# Board.net
KiCad netlist of a schematic drawn in EAGLE
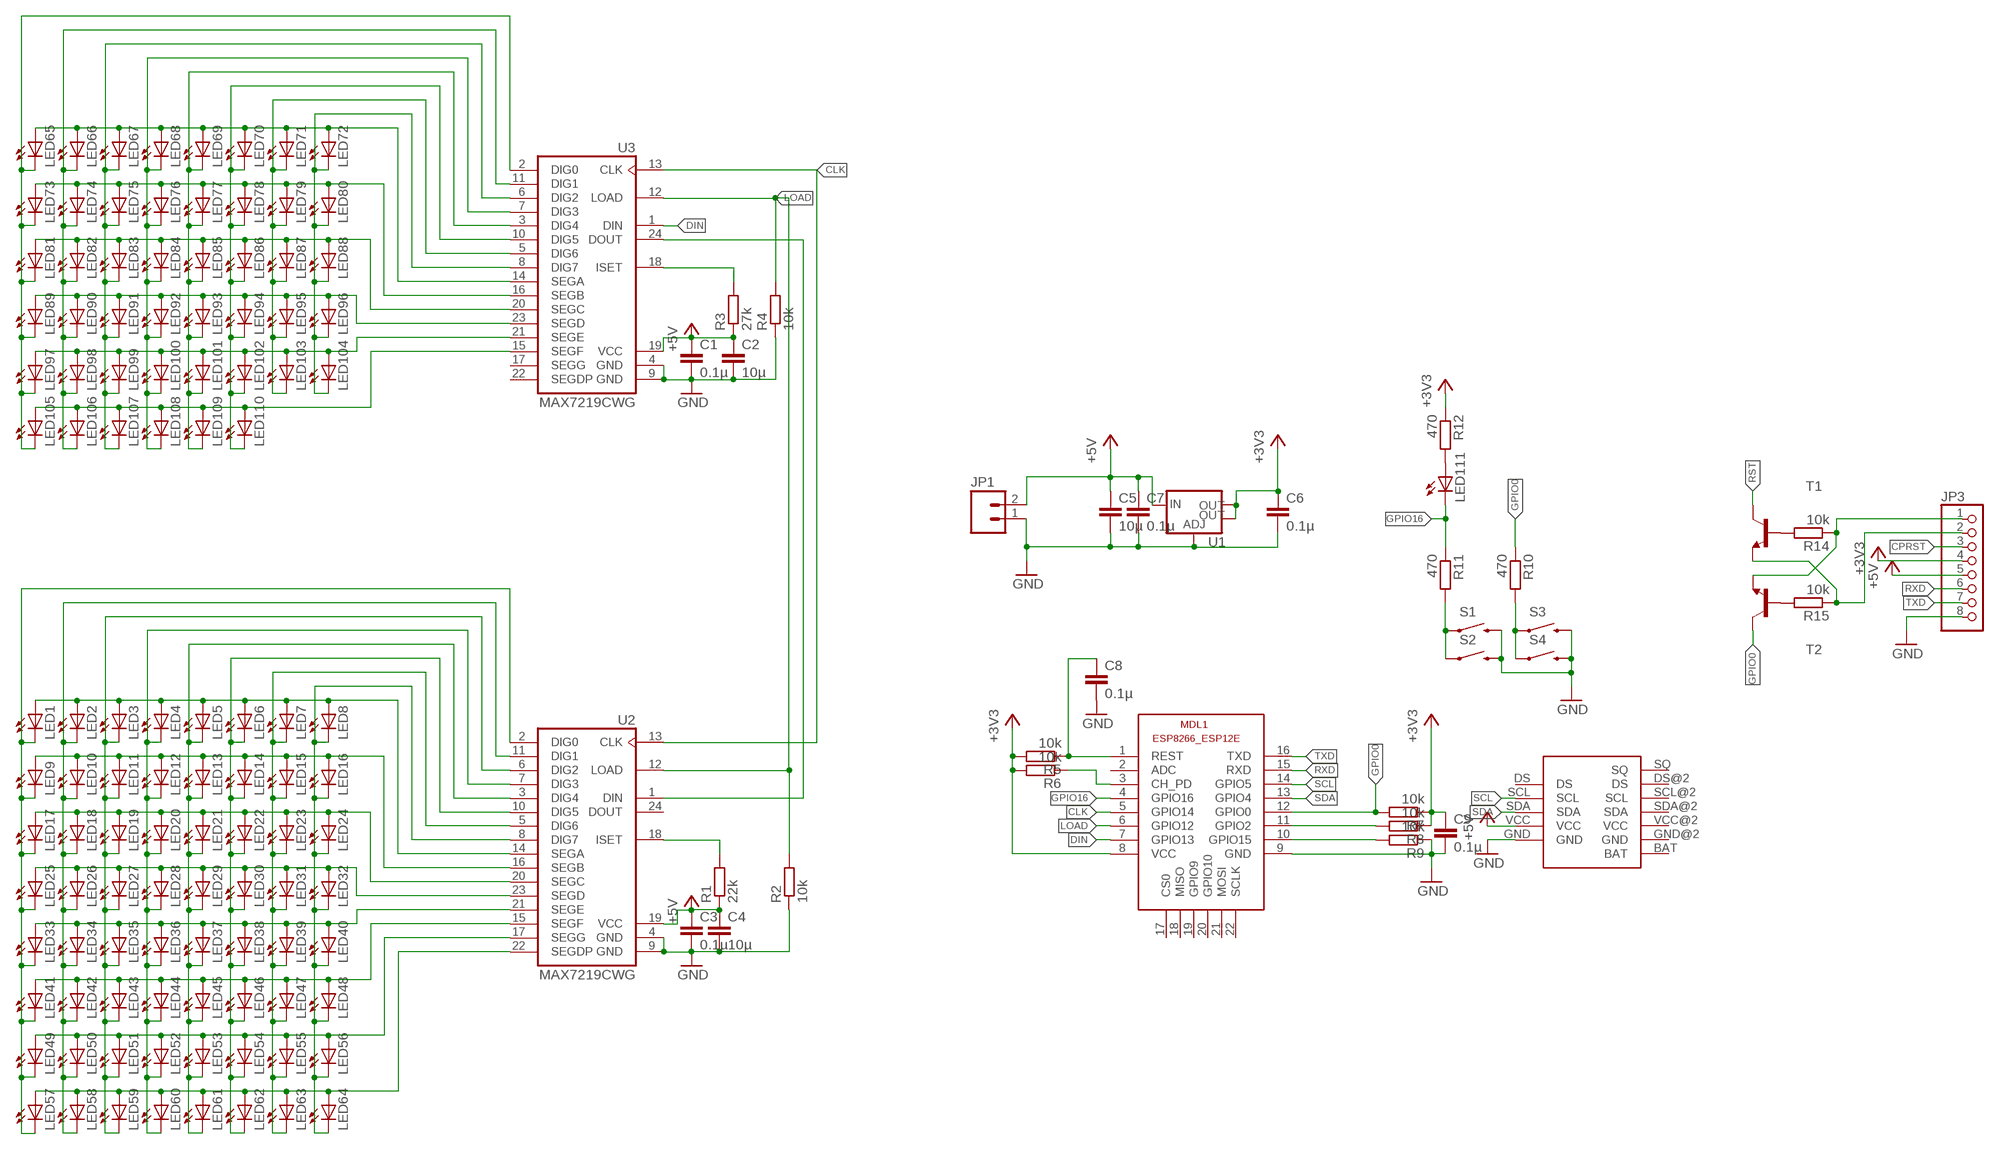
[diagram p0: schematic, sheet 1]

(export (version "E")
  (design (tool "Eeschema 10.0.6"))
  (components
    (comp (ref "C1")
      (value "0.1µ")
      (footprint "eagle-import:C0603")
      (libsource (lib "eagle-import") (part "C-EUC0603"))
    )
    (comp (ref "C2")
      (value "10µ")
      (footprint "eagle-import:C0603")
      (libsource (lib "eagle-import") (part "C-EUC0603"))
    )
    (comp (ref "C3")
      (value "0.1µ")
      (footprint "eagle-import:C0603")
      (libsource (lib "eagle-import") (part "C-EUC0603"))
    )
    (comp (ref "C4")
      (value "10µ")
      (footprint "eagle-import:C0603")
      (libsource (lib "eagle-import") (part "C-EUC0603"))
    )
    (comp (ref "C5")
      (value "10µ")
      (footprint "eagle-import:C0603")
      (libsource (lib "eagle-import") (part "C-EUC0603"))
    )
    (comp (ref "C6")
      (value "0.1µ")
      (footprint "eagle-import:C0603")
      (libsource (lib "eagle-import") (part "C-EUC0603"))
    )
    (comp (ref "C7")
      (value "0.1µ")
      (footprint "eagle-import:C0603")
      (libsource (lib "eagle-import") (part "C-EUC0603"))
    )
    (comp (ref "C8")
      (value "0.1µ")
      (footprint "eagle-import:C0603")
      (libsource (lib "eagle-import") (part "C-EUC0603"))
    )
    (comp (ref "C9")
      (value "0.1µ")
      (footprint "eagle-import:C0603")
      (libsource (lib "eagle-import") (part "C-EUC0603"))
    )
    (comp (ref "JP1")
      (value "M02POLAR")
      (footprint "eagle-import:MOLEX-1X2")
      (libsource (lib "eagle-import") (part "M02POLAR"))
    )
    (comp (ref "JP3")
      (value "PINHD-1X8")
      (footprint "eagle-import:1X08")
      (libsource (lib "eagle-import") (part "PINHD-1X8"))
    )
    (comp (ref "LED1")
      (value "LEDCHIPLED_0805")
      (footprint "eagle-import:CHIPLED_0805")
      (libsource (lib "eagle-import") (part "LEDCHIPLED_0805"))
    )
    (comp (ref "LED2")
      (value "LEDCHIPLED_0805")
      (footprint "eagle-import:CHIPLED_0805")
      (libsource (lib "eagle-import") (part "LEDCHIPLED_0805"))
    )
    (comp (ref "LED3")
      (value "LEDCHIPLED_0805")
      (footprint "eagle-import:CHIPLED_0805")
      (libsource (lib "eagle-import") (part "LEDCHIPLED_0805"))
    )
    (comp (ref "LED4")
      (value "LEDCHIPLED_0805")
      (footprint "eagle-import:CHIPLED_0805")
      (libsource (lib "eagle-import") (part "LEDCHIPLED_0805"))
    )
    (comp (ref "LED5")
      (value "LEDCHIPLED_0805")
      (footprint "eagle-import:CHIPLED_0805")
      (libsource (lib "eagle-import") (part "LEDCHIPLED_0805"))
    )
    (comp (ref "LED6")
      (value "LEDCHIPLED_0805")
      (footprint "eagle-import:CHIPLED_0805")
      (libsource (lib "eagle-import") (part "LEDCHIPLED_0805"))
    )
    (comp (ref "LED7")
      (value "LEDCHIPLED_0805")
      (footprint "eagle-import:CHIPLED_0805")
      (libsource (lib "eagle-import") (part "LEDCHIPLED_0805"))
    )
    (comp (ref "LED8")
      (value "LEDCHIPLED_0805")
      (footprint "eagle-import:CHIPLED_0805")
      (libsource (lib "eagle-import") (part "LEDCHIPLED_0805"))
    )
    (comp (ref "LED9")
      (value "LEDCHIPLED_0805")
      (footprint "eagle-import:CHIPLED_0805")
      (libsource (lib "eagle-import") (part "LEDCHIPLED_0805"))
    )
    (comp (ref "LED10")
      (value "LEDCHIPLED_0805")
      (footprint "eagle-import:CHIPLED_0805")
      (libsource (lib "eagle-import") (part "LEDCHIPLED_0805"))
    )
    (comp (ref "LED11")
      (value "LEDCHIPLED_0805")
      (footprint "eagle-import:CHIPLED_0805")
      (libsource (lib "eagle-import") (part "LEDCHIPLED_0805"))
    )
    (comp (ref "LED12")
      (value "LEDCHIPLED_0805")
      (footprint "eagle-import:CHIPLED_0805")
      (libsource (lib "eagle-import") (part "LEDCHIPLED_0805"))
    )
    (comp (ref "LED13")
      (value "LEDCHIPLED_0805")
      (footprint "eagle-import:CHIPLED_0805")
      (libsource (lib "eagle-import") (part "LEDCHIPLED_0805"))
    )
    (comp (ref "LED14")
      (value "LEDCHIPLED_0805")
      (footprint "eagle-import:CHIPLED_0805")
      (libsource (lib "eagle-import") (part "LEDCHIPLED_0805"))
    )
    (comp (ref "LED15")
      (value "LEDCHIPLED_0805")
      (footprint "eagle-import:CHIPLED_0805")
      (libsource (lib "eagle-import") (part "LEDCHIPLED_0805"))
    )
    (comp (ref "LED16")
      (value "LEDCHIPLED_0805")
      (footprint "eagle-import:CHIPLED_0805")
      (libsource (lib "eagle-import") (part "LEDCHIPLED_0805"))
    )
    (comp (ref "LED17")
      (value "LEDCHIPLED_0805")
      (footprint "eagle-import:CHIPLED_0805")
      (libsource (lib "eagle-import") (part "LEDCHIPLED_0805"))
    )
    (comp (ref "LED18")
      (value "LEDCHIPLED_0805")
      (footprint "eagle-import:CHIPLED_0805")
      (libsource (lib "eagle-import") (part "LEDCHIPLED_0805"))
    )
    (comp (ref "LED19")
      (value "LEDCHIPLED_0805")
      (footprint "eagle-import:CHIPLED_0805")
      (libsource (lib "eagle-import") (part "LEDCHIPLED_0805"))
    )
    (comp (ref "LED20")
      (value "LEDCHIPLED_0805")
      (footprint "eagle-import:CHIPLED_0805")
      (libsource (lib "eagle-import") (part "LEDCHIPLED_0805"))
    )
    (comp (ref "LED21")
      (value "LEDCHIPLED_0805")
      (footprint "eagle-import:CHIPLED_0805")
      (libsource (lib "eagle-import") (part "LEDCHIPLED_0805"))
    )
    (comp (ref "LED22")
      (value "LEDCHIPLED_0805")
      (footprint "eagle-import:CHIPLED_0805")
      (libsource (lib "eagle-import") (part "LEDCHIPLED_0805"))
    )
    (comp (ref "LED23")
      (value "LEDCHIPLED_0805")
      (footprint "eagle-import:CHIPLED_0805")
      (libsource (lib "eagle-import") (part "LEDCHIPLED_0805"))
    )
    (comp (ref "LED24")
      (value "LEDCHIPLED_0805")
      (footprint "eagle-import:CHIPLED_0805")
      (libsource (lib "eagle-import") (part "LEDCHIPLED_0805"))
    )
    (comp (ref "LED25")
      (value "LEDCHIPLED_0805")
      (footprint "eagle-import:CHIPLED_0805")
      (libsource (lib "eagle-import") (part "LEDCHIPLED_0805"))
    )
    (comp (ref "LED26")
      (value "LEDCHIPLED_0805")
      (footprint "eagle-import:CHIPLED_0805")
      (libsource (lib "eagle-import") (part "LEDCHIPLED_0805"))
    )
    (comp (ref "LED27")
      (value "LEDCHIPLED_0805")
      (footprint "eagle-import:CHIPLED_0805")
      (libsource (lib "eagle-import") (part "LEDCHIPLED_0805"))
    )
    (comp (ref "LED28")
      (value "LEDCHIPLED_0805")
      (footprint "eagle-import:CHIPLED_0805")
      (libsource (lib "eagle-import") (part "LEDCHIPLED_0805"))
    )
    (comp (ref "LED29")
      (value "LEDCHIPLED_0805")
      (footprint "eagle-import:CHIPLED_0805")
      (libsource (lib "eagle-import") (part "LEDCHIPLED_0805"))
    )
    (comp (ref "LED30")
      (value "LEDCHIPLED_0805")
      (footprint "eagle-import:CHIPLED_0805")
      (libsource (lib "eagle-import") (part "LEDCHIPLED_0805"))
    )
    (comp (ref "LED31")
      (value "LEDCHIPLED_0805")
      (footprint "eagle-import:CHIPLED_0805")
      (libsource (lib "eagle-import") (part "LEDCHIPLED_0805"))
    )
    (comp (ref "LED32")
      (value "LEDCHIPLED_0805")
      (footprint "eagle-import:CHIPLED_0805")
      (libsource (lib "eagle-import") (part "LEDCHIPLED_0805"))
    )
    (comp (ref "LED33")
      (value "LEDCHIPLED_0805")
      (footprint "eagle-import:CHIPLED_0805")
      (libsource (lib "eagle-import") (part "LEDCHIPLED_0805"))
    )
    (comp (ref "LED34")
      (value "LEDCHIPLED_0805")
      (footprint "eagle-import:CHIPLED_0805")
      (libsource (lib "eagle-import") (part "LEDCHIPLED_0805"))
    )
    (comp (ref "LED35")
      (value "LEDCHIPLED_0805")
      (footprint "eagle-import:CHIPLED_0805")
      (libsource (lib "eagle-import") (part "LEDCHIPLED_0805"))
    )
    (comp (ref "LED36")
      (value "LEDCHIPLED_0805")
      (footprint "eagle-import:CHIPLED_0805")
      (libsource (lib "eagle-import") (part "LEDCHIPLED_0805"))
    )
    (comp (ref "LED37")
      (value "LEDCHIPLED_0805")
      (footprint "eagle-import:CHIPLED_0805")
      (libsource (lib "eagle-import") (part "LEDCHIPLED_0805"))
    )
    (comp (ref "LED38")
      (value "LEDCHIPLED_0805")
      (footprint "eagle-import:CHIPLED_0805")
      (libsource (lib "eagle-import") (part "LEDCHIPLED_0805"))
    )
    (comp (ref "LED39")
      (value "LEDCHIPLED_0805")
      (footprint "eagle-import:CHIPLED_0805")
      (libsource (lib "eagle-import") (part "LEDCHIPLED_0805"))
    )
    (comp (ref "LED40")
      (value "LEDCHIPLED_0805")
      (footprint "eagle-import:CHIPLED_0805")
      (libsource (lib "eagle-import") (part "LEDCHIPLED_0805"))
    )
    (comp (ref "LED41")
      (value "LEDCHIPLED_0805")
      (footprint "eagle-import:CHIPLED_0805")
      (libsource (lib "eagle-import") (part "LEDCHIPLED_0805"))
    )
    (comp (ref "LED42")
      (value "LEDCHIPLED_0805")
      (footprint "eagle-import:CHIPLED_0805")
      (libsource (lib "eagle-import") (part "LEDCHIPLED_0805"))
    )
    (comp (ref "LED43")
      (value "LEDCHIPLED_0805")
      (footprint "eagle-import:CHIPLED_0805")
      (libsource (lib "eagle-import") (part "LEDCHIPLED_0805"))
    )
    (comp (ref "LED44")
      (value "LEDCHIPLED_0805")
      (footprint "eagle-import:CHIPLED_0805")
      (libsource (lib "eagle-import") (part "LEDCHIPLED_0805"))
    )
    (comp (ref "LED45")
      (value "LEDCHIPLED_0805")
      (footprint "eagle-import:CHIPLED_0805")
      (libsource (lib "eagle-import") (part "LEDCHIPLED_0805"))
    )
    (comp (ref "LED46")
      (value "LEDCHIPLED_0805")
      (footprint "eagle-import:CHIPLED_0805")
      (libsource (lib "eagle-import") (part "LEDCHIPLED_0805"))
    )
    (comp (ref "LED47")
      (value "LEDCHIPLED_0805")
      (footprint "eagle-import:CHIPLED_0805")
      (libsource (lib "eagle-import") (part "LEDCHIPLED_0805"))
    )
    (comp (ref "LED48")
      (value "LEDCHIPLED_0805")
      (footprint "eagle-import:CHIPLED_0805")
      (libsource (lib "eagle-import") (part "LEDCHIPLED_0805"))
    )
    (comp (ref "LED49")
      (value "LEDCHIPLED_0805")
      (footprint "eagle-import:CHIPLED_0805")
      (libsource (lib "eagle-import") (part "LEDCHIPLED_0805"))
    )
    (comp (ref "LED50")
      (value "LEDCHIPLED_0805")
      (footprint "eagle-import:CHIPLED_0805")
      (libsource (lib "eagle-import") (part "LEDCHIPLED_0805"))
    )
    (comp (ref "LED51")
      (value "LEDCHIPLED_0805")
      (footprint "eagle-import:CHIPLED_0805")
      (libsource (lib "eagle-import") (part "LEDCHIPLED_0805"))
    )
    (comp (ref "LED52")
      (value "LEDCHIPLED_0805")
      (footprint "eagle-import:CHIPLED_0805")
      (libsource (lib "eagle-import") (part "LEDCHIPLED_0805"))
    )
    (comp (ref "LED53")
      (value "LEDCHIPLED_0805")
      (footprint "eagle-import:CHIPLED_0805")
      (libsource (lib "eagle-import") (part "LEDCHIPLED_0805"))
    )
    (comp (ref "LED54")
      (value "LEDCHIPLED_0805")
      (footprint "eagle-import:CHIPLED_0805")
      (libsource (lib "eagle-import") (part "LEDCHIPLED_0805"))
    )
    (comp (ref "LED55")
      (value "LEDCHIPLED_0805")
      (footprint "eagle-import:CHIPLED_0805")
      (libsource (lib "eagle-import") (part "LEDCHIPLED_0805"))
    )
    (comp (ref "LED56")
      (value "LEDCHIPLED_0805")
      (footprint "eagle-import:CHIPLED_0805")
      (libsource (lib "eagle-import") (part "LEDCHIPLED_0805"))
    )
    (comp (ref "LED57")
      (value "LEDCHIPLED_0805")
      (footprint "eagle-import:CHIPLED_0805")
      (libsource (lib "eagle-import") (part "LEDCHIPLED_0805"))
    )
    (comp (ref "LED58")
      (value "LEDCHIPLED_0805")
      (footprint "eagle-import:CHIPLED_0805")
      (libsource (lib "eagle-import") (part "LEDCHIPLED_0805"))
    )
    (comp (ref "LED59")
      (value "LEDCHIPLED_0805")
      (footprint "eagle-import:CHIPLED_0805")
      (libsource (lib "eagle-import") (part "LEDCHIPLED_0805"))
    )
    (comp (ref "LED60")
      (value "LEDCHIPLED_0805")
      (footprint "eagle-import:CHIPLED_0805")
      (libsource (lib "eagle-import") (part "LEDCHIPLED_0805"))
    )
    (comp (ref "LED61")
      (value "LEDCHIPLED_0805")
      (footprint "eagle-import:CHIPLED_0805")
      (libsource (lib "eagle-import") (part "LEDCHIPLED_0805"))
    )
    (comp (ref "LED62")
      (value "LEDCHIPLED_0805")
      (footprint "eagle-import:CHIPLED_0805")
      (libsource (lib "eagle-import") (part "LEDCHIPLED_0805"))
    )
    (comp (ref "LED63")
      (value "LEDCHIPLED_0805")
      (footprint "eagle-import:CHIPLED_0805")
      (libsource (lib "eagle-import") (part "LEDCHIPLED_0805"))
    )
    (comp (ref "LED64")
      (value "LEDCHIPLED_0805")
      (footprint "eagle-import:CHIPLED_0805")
      (libsource (lib "eagle-import") (part "LEDCHIPLED_0805"))
    )
    (comp (ref "LED65")
      (value "LEDCHIPLED_0805")
      (footprint "eagle-import:CHIPLED_0805")
      (libsource (lib "eagle-import") (part "LEDCHIPLED_0805"))
    )
    (comp (ref "LED66")
      (value "LEDCHIPLED_0805")
      (footprint "eagle-import:CHIPLED_0805")
      (libsource (lib "eagle-import") (part "LEDCHIPLED_0805"))
    )
    (comp (ref "LED67")
      (value "LEDCHIPLED_0805")
      (footprint "eagle-import:CHIPLED_0805")
      (libsource (lib "eagle-import") (part "LEDCHIPLED_0805"))
    )
    (comp (ref "LED68")
      (value "LEDCHIPLED_0805")
      (footprint "eagle-import:CHIPLED_0805")
      (libsource (lib "eagle-import") (part "LEDCHIPLED_0805"))
    )
    (comp (ref "LED69")
      (value "LEDCHIPLED_0805")
      (footprint "eagle-import:CHIPLED_0805")
      (libsource (lib "eagle-import") (part "LEDCHIPLED_0805"))
    )
    (comp (ref "LED70")
      (value "LEDCHIPLED_0805")
      (footprint "eagle-import:CHIPLED_0805")
      (libsource (lib "eagle-import") (part "LEDCHIPLED_0805"))
    )
    (comp (ref "LED71")
      (value "LEDCHIPLED_0805")
      (footprint "eagle-import:CHIPLED_0805")
      (libsource (lib "eagle-import") (part "LEDCHIPLED_0805"))
    )
    (comp (ref "LED72")
      (value "LEDCHIPLED_0805")
      (footprint "eagle-import:CHIPLED_0805")
      (libsource (lib "eagle-import") (part "LEDCHIPLED_0805"))
    )
    (comp (ref "LED73")
      (value "LEDCHIPLED_0805")
      (footprint "eagle-import:CHIPLED_0805")
      (libsource (lib "eagle-import") (part "LEDCHIPLED_0805"))
    )
    (comp (ref "LED74")
      (value "LEDCHIPLED_0805")
      (footprint "eagle-import:CHIPLED_0805")
      (libsource (lib "eagle-import") (part "LEDCHIPLED_0805"))
    )
    (comp (ref "LED75")
      (value "LEDCHIPLED_0805")
      (footprint "eagle-import:CHIPLED_0805")
      (libsource (lib "eagle-import") (part "LEDCHIPLED_0805"))
    )
    (comp (ref "LED76")
      (value "LEDCHIPLED_0805")
      (footprint "eagle-import:CHIPLED_0805")
      (libsource (lib "eagle-import") (part "LEDCHIPLED_0805"))
    )
    (comp (ref "LED77")
      (value "LEDCHIPLED_0805")
      (footprint "eagle-import:CHIPLED_0805")
      (libsource (lib "eagle-import") (part "LEDCHIPLED_0805"))
    )
    (comp (ref "LED78")
      (value "LEDCHIPLED_0805")
      (footprint "eagle-import:CHIPLED_0805")
      (libsource (lib "eagle-import") (part "LEDCHIPLED_0805"))
    )
    (comp (ref "LED79")
      (value "LEDCHIPLED_0805")
      (footprint "eagle-import:CHIPLED_0805")
      (libsource (lib "eagle-import") (part "LEDCHIPLED_0805"))
    )
    (comp (ref "LED80")
      (value "LEDCHIPLED_0805")
      (footprint "eagle-import:CHIPLED_0805")
      (libsource (lib "eagle-import") (part "LEDCHIPLED_0805"))
    )
    (comp (ref "LED81")
      (value "LEDCHIPLED_0805")
      (footprint "eagle-import:CHIPLED_0805")
      (libsource (lib "eagle-import") (part "LEDCHIPLED_0805"))
    )
    (comp (ref "LED82")
      (value "LEDCHIPLED_0805")
      (footprint "eagle-import:CHIPLED_0805")
      (libsource (lib "eagle-import") (part "LEDCHIPLED_0805"))
    )
    (comp (ref "LED83")
      (value "LEDCHIPLED_0805")
      (footprint "eagle-import:CHIPLED_0805")
      (libsource (lib "eagle-import") (part "LEDCHIPLED_0805"))
    )
    (comp (ref "LED84")
      (value "LEDCHIPLED_0805")
      (footprint "eagle-import:CHIPLED_0805")
      (libsource (lib "eagle-import") (part "LEDCHIPLED_0805"))
    )
    (comp (ref "LED85")
      (value "LEDCHIPLED_0805")
      (footprint "eagle-import:CHIPLED_0805")
      (libsource (lib "eagle-import") (part "LEDCHIPLED_0805"))
    )
    (comp (ref "LED86")
      (value "LEDCHIPLED_0805")
      (footprint "eagle-import:CHIPLED_0805")
      (libsource (lib "eagle-import") (part "LEDCHIPLED_0805"))
    )
    (comp (ref "LED87")
      (value "LEDCHIPLED_0805")
      (footprint "eagle-import:CHIPLED_0805")
      (libsource (lib "eagle-import") (part "LEDCHIPLED_0805"))
    )
    (comp (ref "LED88")
      (value "LEDCHIPLED_0805")
      (footprint "eagle-import:CHIPLED_0805")
      (libsource (lib "eagle-import") (part "LEDCHIPLED_0805"))
    )
    (comp (ref "LED89")
      (value "LEDCHIPLED_0805")
      (footprint "eagle-import:CHIPLED_0805")
      (libsource (lib "eagle-import") (part "LEDCHIPLED_0805"))
    )
    (comp (ref "LED90")
      (value "LEDCHIPLED_0805")
      (footprint "eagle-import:CHIPLED_0805")
      (libsource (lib "eagle-import") (part "LEDCHIPLED_0805"))
    )
    (comp (ref "LED91")
      (value "LEDCHIPLED_0805")
      (footprint "eagle-import:CHIPLED_0805")
      (libsource (lib "eagle-import") (part "LEDCHIPLED_0805"))
    )
    (comp (ref "LED92")
      (value "LEDCHIPLED_0805")
      (footprint "eagle-import:CHIPLED_0805")
      (libsource (lib "eagle-import") (part "LEDCHIPLED_0805"))
    )
    (comp (ref "LED93")
      (value "LEDCHIPLED_0805")
      (footprint "eagle-import:CHIPLED_0805")
      (libsource (lib "eagle-import") (part "LEDCHIPLED_0805"))
    )
    (comp (ref "LED94")
      (value "LEDCHIPLED_0805")
      (footprint "eagle-import:CHIPLED_0805")
      (libsource (lib "eagle-import") (part "LEDCHIPLED_0805"))
    )
    (comp (ref "LED95")
      (value "LEDCHIPLED_0805")
      (footprint "eagle-import:CHIPLED_0805")
      (libsource (lib "eagle-import") (part "LEDCHIPLED_0805"))
    )
    (comp (ref "LED96")
      (value "LEDCHIPLED_0805")
      (footprint "eagle-import:CHIPLED_0805")
      (libsource (lib "eagle-import") (part "LEDCHIPLED_0805"))
    )
    (comp (ref "LED97")
      (value "LEDCHIPLED_0805")
      (footprint "eagle-import:CHIPLED_0805")
      (libsource (lib "eagle-import") (part "LEDCHIPLED_0805"))
    )
    (comp (ref "LED98")
      (value "LEDCHIPLED_0805")
      (footprint "eagle-import:CHIPLED_0805")
      (libsource (lib "eagle-import") (part "LEDCHIPLED_0805"))
    )
    (comp (ref "LED99")
      (value "LEDCHIPLED_0805")
      (footprint "eagle-import:CHIPLED_0805")
      (libsource (lib "eagle-import") (part "LEDCHIPLED_0805"))
    )
    (comp (ref "LED100")
      (value "LEDCHIPLED_0805")
      (footprint "eagle-import:CHIPLED_0805")
      (libsource (lib "eagle-import") (part "LEDCHIPLED_0805"))
    )
    (comp (ref "LED101")
      (value "LEDCHIPLED_0805")
      (footprint "eagle-import:CHIPLED_0805")
      (libsource (lib "eagle-import") (part "LEDCHIPLED_0805"))
    )
    (comp (ref "LED102")
      (value "LEDCHIPLED_0805")
      (footprint "eagle-import:CHIPLED_0805")
      (libsource (lib "eagle-import") (part "LEDCHIPLED_0805"))
    )
    (comp (ref "LED103")
      (value "LEDCHIPLED_0805")
      (footprint "eagle-import:CHIPLED_0805")
      (libsource (lib "eagle-import") (part "LEDCHIPLED_0805"))
    )
    (comp (ref "LED104")
      (value "LEDCHIPLED_0805")
      (footprint "eagle-import:CHIPLED_0805")
      (libsource (lib "eagle-import") (part "LEDCHIPLED_0805"))
    )
    (comp (ref "LED105")
      (value "LEDCHIPLED_0805")
      (footprint "eagle-import:CHIPLED_0805")
      (libsource (lib "eagle-import") (part "LEDCHIPLED_0805"))
    )
    (comp (ref "LED106")
      (value "LEDCHIPLED_0805")
      (footprint "eagle-import:CHIPLED_0805")
      (libsource (lib "eagle-import") (part "LEDCHIPLED_0805"))
    )
    (comp (ref "LED107")
      (value "LEDCHIPLED_0805")
      (footprint "eagle-import:CHIPLED_0805")
      (libsource (lib "eagle-import") (part "LEDCHIPLED_0805"))
    )
    (comp (ref "LED108")
      (value "LEDCHIPLED_0805")
      (footprint "eagle-import:CHIPLED_0805")
      (libsource (lib "eagle-import") (part "LEDCHIPLED_0805"))
    )
    (comp (ref "LED109")
      (value "LEDCHIPLED_0805")
      (footprint "eagle-import:CHIPLED_0805")
      (libsource (lib "eagle-import") (part "LEDCHIPLED_0805"))
    )
    (comp (ref "LED110")
      (value "LEDCHIPLED_0805")
      (footprint "eagle-import:CHIPLED_0805")
      (libsource (lib "eagle-import") (part "LEDCHIPLED_0805"))
    )
    (comp (ref "LED111")
      (value "LEDCHIPLED_0805")
      (footprint "eagle-import:CHIPLED_0805")
      (libsource (lib "eagle-import") (part "LEDCHIPLED_0805"))
    )
    (comp (ref "MDL1")
      (value "ESP8266-12EESP8266-ESP12E")
      (footprint "eagle-import:ESP8266-ESP12E")
      (libsource (lib "eagle-import") (part "ESP8266-12EESP8266-ESP12E"))
    )
    (comp (ref "R1")
      (value "22k")
      (footprint "eagle-import:R0603")
      (libsource (lib "eagle-import") (part "R-EU_R0603"))
    )
    (comp (ref "R2")
      (value "10k")
      (footprint "eagle-import:R0603")
      (libsource (lib "eagle-import") (part "R-EU_R0603"))
    )
    (comp (ref "R3")
      (value "27k")
      (footprint "eagle-import:R0603")
      (libsource (lib "eagle-import") (part "R-EU_R0603"))
    )
    (comp (ref "R4")
      (value "10k")
      (footprint "eagle-import:R0603")
      (libsource (lib "eagle-import") (part "R-EU_R0603"))
    )
    (comp (ref "R5")
      (value "10k")
      (footprint "eagle-import:R0603")
      (libsource (lib "eagle-import") (part "R-EU_R0603"))
    )
    (comp (ref "R6")
      (value "10k")
      (footprint "eagle-import:R0603")
      (libsource (lib "eagle-import") (part "R-EU_R0603"))
    )
    (comp (ref "R7")
      (value "10k")
      (footprint "eagle-import:R0603")
      (libsource (lib "eagle-import") (part "R-EU_R0603"))
    )
    (comp (ref "R8")
      (value "10k")
      (footprint "eagle-import:R0603")
      (libsource (lib "eagle-import") (part "R-EU_R0603"))
    )
    (comp (ref "R9")
      (value "10k")
      (footprint "eagle-import:R0603")
      (libsource (lib "eagle-import") (part "R-EU_R0603"))
    )
    (comp (ref "R10")
      (value "470")
      (footprint "eagle-import:R0603")
      (libsource (lib "eagle-import") (part "R-EU_R0603"))
    )
    (comp (ref "R11")
      (value "470")
      (footprint "eagle-import:R0603")
      (libsource (lib "eagle-import") (part "R-EU_R0603"))
    )
    (comp (ref "R12")
      (value "470")
      (footprint "eagle-import:R0603")
      (libsource (lib "eagle-import") (part "R-EU_R0603"))
    )
    (comp (ref "R14")
      (value "10k")
      (footprint "eagle-import:R0603")
      (libsource (lib "eagle-import") (part "R-EU_R0603"))
    )
    (comp (ref "R15")
      (value "10k")
      (footprint "eagle-import:R0603")
      (libsource (lib "eagle-import") (part "R-EU_R0603"))
    )
    (comp (ref "S1")
      (value "SWITCH-MOMENTARY-2SIDE_EZ")
      (footprint "eagle-import:TACTILE-PTH-SIDEEZ")
      (libsource (lib "eagle-import") (part "SWITCH-MOMENTARY-2SIDE_EZ"))
    )
    (comp (ref "S2")
      (value "SWITCH-MOMENTARY-2SMD-1101NE")
      (footprint "eagle-import:TACTILE-SWITCH-1101NE")
      (libsource (lib "eagle-import") (part "SWITCH-MOMENTARY-2SMD-1101NE"))
    )
    (comp (ref "S3")
      (value "SWITCH-MOMENTARY-2SIDE_EZ")
      (footprint "eagle-import:TACTILE-PTH-SIDEEZ")
      (libsource (lib "eagle-import") (part "SWITCH-MOMENTARY-2SIDE_EZ"))
    )
    (comp (ref "S4")
      (value "SWITCH-MOMENTARY-2SMD-1101NE")
      (footprint "eagle-import:TACTILE-SWITCH-1101NE")
      (libsource (lib "eagle-import") (part "SWITCH-MOMENTARY-2SMD-1101NE"))
    )
    (comp (ref "T1")
      (value "BC847-NPN-SOT23-BEC")
      (footprint "eagle-import:SOT23-BEC")
      (libsource (lib "eagle-import") (part "-NPN-SOT23-BECBC847"))
    )
    (comp (ref "T2")
      (value "BC847-NPN-SOT23-BEC")
      (footprint "eagle-import:SOT23-BEC")
      (libsource (lib "eagle-import") (part "-NPN-SOT23-BECBC847"))
    )
    (comp (ref "U$3")
      (value "DS1307-MODULE")
      (footprint "eagle-import:DS1307-MODULE")
      (libsource (lib "eagle-import") (part "DS1307-MODULE"))
    )
    (comp (ref "U1")
      (value "V_REG_LM1117SOT223")
      (footprint "eagle-import:SOT223")
      (libsource (lib "eagle-import") (part "V_REG_LM1117SOT223"))
    )
    (comp (ref "U2")
      (value "MAX7219CWG")
      (footprint "eagle-import:SO24L")
      (libsource (lib "eagle-import") (part "MAX7219CWG"))
    )
    (comp (ref "U3")
      (value "MAX7219CWG")
      (footprint "eagle-import:SO24L")
      (libsource (lib "eagle-import") (part "MAX7219CWG"))
    )
  )
  (nets
    (net (code "1") (name "+3V3") (class "Default")
      (node (ref "C6") (pin "1") (pinfunction "1_1") (pintype "passive"))
      (node (ref "C9") (pin "1") (pinfunction "1_1") (pintype "passive"))
      (node (ref "JP3") (pin "4") (pinfunction "4_4") (pintype "passive"))
      (node (ref "MDL1") (pin "8") (pinfunction "VCC_8") (pintype "bidirectional"))
      (node (ref "R12") (pin "1") (pinfunction "1_1") (pintype "passive"))
      (node (ref "R5") (pin "2") (pinfunction "2_2") (pintype "passive"))
      (node (ref "R6") (pin "2") (pinfunction "2_2") (pintype "passive"))
      (node (ref "R7") (pin "1") (pinfunction "1_1") (pintype "passive"))
      (node (ref "R8") (pin "1") (pinfunction "1_1") (pintype "passive"))
      (node (ref "U1") (pin "2") (pinfunction "OUT_2") (pintype "output"))
      (node (ref "U1") (pin "4") (pinfunction "OUT_4") (pintype "output"))
    )
    (net (code "2") (name "+5V") (class "Default")
      (node (ref "C1") (pin "1") (pinfunction "1_1") (pintype "passive"))
      (node (ref "C2") (pin "1") (pinfunction "1_1") (pintype "passive"))
      (node (ref "C3") (pin "1") (pinfunction "1_1") (pintype "passive"))
      (node (ref "C4") (pin "1") (pinfunction "1_1") (pintype "passive"))
      (node (ref "C5") (pin "1") (pinfunction "1_1") (pintype "passive"))
      (node (ref "C7") (pin "1") (pinfunction "1_1") (pintype "passive"))
      (node (ref "JP1") (pin "2") (pinfunction "2_2") (pintype "passive"))
      (node (ref "JP3") (pin "5") (pinfunction "5_5") (pintype "passive"))
      (node (ref "R1") (pin "1") (pinfunction "1_1") (pintype "passive"))
      (node (ref "R3") (pin "1") (pinfunction "1_1") (pintype "passive"))
      (node (ref "U$3") (pin "VCC") (pinfunction "VCC_VCC") (pintype "bidirectional"))
      (node (ref "U1") (pin "3") (pinfunction "IN_3") (pintype "input"))
      (node (ref "U2") (pin "19") (pinfunction "VCC_19") (pintype "power_in"))
      (node (ref "U3") (pin "19") (pinfunction "VCC_19") (pintype "power_in"))
    )
    (net (code "3") (name "CLK") (class "Default")
      (node (ref "MDL1") (pin "5") (pinfunction "GPIO14_5") (pintype "bidirectional"))
      (node (ref "U2") (pin "13") (pinfunction "CLK_13") (pintype "input"))
      (node (ref "U3") (pin "13") (pinfunction "CLK_13") (pintype "input"))
    )
    (net (code "4") (name "CPRST") (class "Default")
      (node (ref "JP3") (pin "3") (pinfunction "3_3") (pintype "passive"))
    )
    (net (code "5") (name "DIN") (class "Default")
      (node (ref "MDL1") (pin "7") (pinfunction "GPIO13_7") (pintype "bidirectional"))
      (node (ref "U3") (pin "1") (pinfunction "DIN_1") (pintype "input"))
    )
    (net (code "6") (name "GND") (class "Default")
      (node (ref "C1") (pin "2") (pinfunction "2_2") (pintype "passive"))
      (node (ref "C2") (pin "2") (pinfunction "2_2") (pintype "passive"))
      (node (ref "C3") (pin "2") (pinfunction "2_2") (pintype "passive"))
      (node (ref "C4") (pin "2") (pinfunction "2_2") (pintype "passive"))
      (node (ref "C5") (pin "2") (pinfunction "2_2") (pintype "passive"))
      (node (ref "C6") (pin "2") (pinfunction "2_2") (pintype "passive"))
      (node (ref "C7") (pin "2") (pinfunction "2_2") (pintype "passive"))
      (node (ref "C8") (pin "2") (pinfunction "2_2") (pintype "passive"))
      (node (ref "C9") (pin "2") (pinfunction "2_2") (pintype "passive"))
      (node (ref "JP1") (pin "1") (pinfunction "1_1") (pintype "passive"))
      (node (ref "JP3") (pin "8") (pinfunction "8_8") (pintype "passive"))
      (node (ref "MDL1") (pin "9") (pinfunction "GND_9") (pintype "bidirectional"))
      (node (ref "R2") (pin "1") (pinfunction "1_1") (pintype "passive"))
      (node (ref "R4") (pin "1") (pinfunction "1_1") (pintype "passive"))
      (node (ref "R9") (pin "1") (pinfunction "1_1") (pintype "passive"))
      (node (ref "S1") (pin "2") (pinfunction "2_2") (pintype "passive"))
      (node (ref "S2") (pin "2") (pinfunction "2_2") (pintype "passive"))
      (node (ref "S3") (pin "2") (pinfunction "2_2") (pintype "passive"))
      (node (ref "S4") (pin "2") (pinfunction "2_2") (pintype "passive"))
      (node (ref "U$3") (pin "GND") (pinfunction "GND_GND") (pintype "bidirectional"))
      (node (ref "U1") (pin "1") (pinfunction "ADJ_1") (pintype "input"))
      (node (ref "U2") (pin "4") (pinfunction "GND_4") (pintype "power_in"))
      (node (ref "U2") (pin "9") (pinfunction "GND_9") (pintype "power_in"))
      (node (ref "U3") (pin "4") (pinfunction "GND_4") (pintype "power_in"))
      (node (ref "U3") (pin "9") (pinfunction "GND_9") (pintype "power_in"))
    )
    (net (code "7") (name "GPIO0") (class "Default")
      (node (ref "MDL1") (pin "12") (pinfunction "GPIO0_12") (pintype "bidirectional"))
      (node (ref "R10") (pin "1") (pinfunction "1_1") (pintype "passive"))
      (node (ref "R7") (pin "2") (pinfunction "2_2") (pintype "passive"))
      (node (ref "T2") (pin "C") (pinfunction "C_C") (pintype "passive"))
    )
    (net (code "8") (name "GPIO16") (class "Default")
      (node (ref "LED111") (pin "C") (pinfunction "C_C") (pintype "passive"))
      (node (ref "MDL1") (pin "4") (pinfunction "GPIO16_4") (pintype "bidirectional"))
      (node (ref "R11") (pin "1") (pinfunction "1_1") (pintype "passive"))
    )
    (net (code "9") (name "LOAD") (class "Default")
      (node (ref "MDL1") (pin "6") (pinfunction "GPIO12_6") (pintype "bidirectional"))
      (node (ref "R2") (pin "2") (pinfunction "2_2") (pintype "passive"))
      (node (ref "R4") (pin "2") (pinfunction "2_2") (pintype "passive"))
      (node (ref "U2") (pin "12") (pinfunction "LOAD_12") (pintype "input"))
      (node (ref "U3") (pin "12") (pinfunction "LOAD_12") (pintype "input"))
    )
    (net (code "10") (name "Net-(JP3-Pad1)") (class "Default")
      (node (ref "JP3") (pin "1") (pinfunction "1_1") (pintype "passive"))
      (node (ref "R14") (pin "1") (pinfunction "1_1") (pintype "passive"))
      (node (ref "T2") (pin "E") (pinfunction "E_E") (pintype "passive"))
    )
    (net (code "11") (name "Net-(JP3-Pad2)") (class "Default")
      (node (ref "JP3") (pin "2") (pinfunction "2_2") (pintype "passive"))
      (node (ref "R15") (pin "1") (pinfunction "1_1") (pintype "passive"))
      (node (ref "T1") (pin "E") (pinfunction "E_E") (pintype "passive"))
    )
    (net (code "12") (name "Net-(LED111-PadA)") (class "Default")
      (node (ref "LED111") (pin "A") (pinfunction "A_A") (pintype "passive"))
      (node (ref "R12") (pin "2") (pinfunction "2_2") (pintype "passive"))
    )
    (net (code "13") (name "Net-(MDL1-CH_PD)") (class "Default")
      (node (ref "MDL1") (pin "3") (pinfunction "CH_PD_3") (pintype "bidirectional"))
      (node (ref "R6") (pin "1") (pinfunction "1_1") (pintype "passive"))
    )
    (net (code "14") (name "Net-(MDL1-GPIO2)") (class "Default")
      (node (ref "MDL1") (pin "11") (pinfunction "GPIO2_11") (pintype "bidirectional"))
      (node (ref "R8") (pin "2") (pinfunction "2_2") (pintype "passive"))
    )
    (net (code "15") (name "Net-(MDL1-GPIO15)") (class "Default")
      (node (ref "MDL1") (pin "10") (pinfunction "GPIO15_10") (pintype "bidirectional"))
      (node (ref "R9") (pin "2") (pinfunction "2_2") (pintype "passive"))
    )
    (net (code "16") (name "Net-(R10-Pad2)") (class "Default")
      (node (ref "R10") (pin "2") (pinfunction "2_2") (pintype "passive"))
      (node (ref "S3") (pin "1") (pinfunction "1_1") (pintype "passive"))
      (node (ref "S4") (pin "1") (pinfunction "1_1") (pintype "passive"))
    )
    (net (code "17") (name "Net-(R11-Pad2)") (class "Default")
      (node (ref "R11") (pin "2") (pinfunction "2_2") (pintype "passive"))
      (node (ref "S1") (pin "1") (pinfunction "1_1") (pintype "passive"))
      (node (ref "S2") (pin "1") (pinfunction "1_1") (pintype "passive"))
    )
    (net (code "18") (name "Net-(R14-Pad2)") (class "Default")
      (node (ref "R14") (pin "2") (pinfunction "2_2") (pintype "passive"))
      (node (ref "T1") (pin "B") (pinfunction "B_B") (pintype "passive"))
    )
    (net (code "19") (name "Net-(R15-Pad2)") (class "Default")
      (node (ref "R15") (pin "2") (pinfunction "2_2") (pintype "passive"))
      (node (ref "T2") (pin "B") (pinfunction "B_B") (pintype "passive"))
    )
    (net (code "20") (name "Net-(U2-DIG0)") (class "Default")
      (node (ref "LED1") (pin "C") (pinfunction "C_C") (pintype "passive"))
      (node (ref "LED17") (pin "C") (pinfunction "C_C") (pintype "passive"))
      (node (ref "LED25") (pin "C") (pinfunction "C_C") (pintype "passive"))
      (node (ref "LED33") (pin "C") (pinfunction "C_C") (pintype "passive"))
      (node (ref "LED41") (pin "C") (pinfunction "C_C") (pintype "passive"))
      (node (ref "LED49") (pin "C") (pinfunction "C_C") (pintype "passive"))
      (node (ref "LED57") (pin "C") (pinfunction "C_C") (pintype "passive"))
      (node (ref "LED9") (pin "C") (pinfunction "C_C") (pintype "passive"))
      (node (ref "U2") (pin "2") (pinfunction "DIG0_2") (pintype "output"))
    )
    (net (code "21") (name "Net-(U2-DIG1)") (class "Default")
      (node (ref "LED10") (pin "C") (pinfunction "C_C") (pintype "passive"))
      (node (ref "LED18") (pin "C") (pinfunction "C_C") (pintype "passive"))
      (node (ref "LED2") (pin "C") (pinfunction "C_C") (pintype "passive"))
      (node (ref "LED26") (pin "C") (pinfunction "C_C") (pintype "passive"))
      (node (ref "LED34") (pin "C") (pinfunction "C_C") (pintype "passive"))
      (node (ref "LED42") (pin "C") (pinfunction "C_C") (pintype "passive"))
      (node (ref "LED50") (pin "C") (pinfunction "C_C") (pintype "passive"))
      (node (ref "LED58") (pin "C") (pinfunction "C_C") (pintype "passive"))
      (node (ref "U2") (pin "11") (pinfunction "DIG1_11") (pintype "output"))
    )
    (net (code "22") (name "Net-(U2-DIG2)") (class "Default")
      (node (ref "LED11") (pin "C") (pinfunction "C_C") (pintype "passive"))
      (node (ref "LED19") (pin "C") (pinfunction "C_C") (pintype "passive"))
      (node (ref "LED27") (pin "C") (pinfunction "C_C") (pintype "passive"))
      (node (ref "LED3") (pin "C") (pinfunction "C_C") (pintype "passive"))
      (node (ref "LED35") (pin "C") (pinfunction "C_C") (pintype "passive"))
      (node (ref "LED43") (pin "C") (pinfunction "C_C") (pintype "passive"))
      (node (ref "LED51") (pin "C") (pinfunction "C_C") (pintype "passive"))
      (node (ref "LED59") (pin "C") (pinfunction "C_C") (pintype "passive"))
      (node (ref "U2") (pin "6") (pinfunction "DIG2_6") (pintype "output"))
    )
    (net (code "23") (name "Net-(U2-DIG3)") (class "Default")
      (node (ref "LED12") (pin "C") (pinfunction "C_C") (pintype "passive"))
      (node (ref "LED20") (pin "C") (pinfunction "C_C") (pintype "passive"))
      (node (ref "LED28") (pin "C") (pinfunction "C_C") (pintype "passive"))
      (node (ref "LED36") (pin "C") (pinfunction "C_C") (pintype "passive"))
      (node (ref "LED4") (pin "C") (pinfunction "C_C") (pintype "passive"))
      (node (ref "LED44") (pin "C") (pinfunction "C_C") (pintype "passive"))
      (node (ref "LED52") (pin "C") (pinfunction "C_C") (pintype "passive"))
      (node (ref "LED60") (pin "C") (pinfunction "C_C") (pintype "passive"))
      (node (ref "U2") (pin "7") (pinfunction "DIG3_7") (pintype "output"))
    )
    (net (code "24") (name "Net-(U2-DIG4)") (class "Default")
      (node (ref "LED13") (pin "C") (pinfunction "C_C") (pintype "passive"))
      (node (ref "LED21") (pin "C") (pinfunction "C_C") (pintype "passive"))
      (node (ref "LED29") (pin "C") (pinfunction "C_C") (pintype "passive"))
      (node (ref "LED37") (pin "C") (pinfunction "C_C") (pintype "passive"))
      (node (ref "LED45") (pin "C") (pinfunction "C_C") (pintype "passive"))
      (node (ref "LED5") (pin "C") (pinfunction "C_C") (pintype "passive"))
      (node (ref "LED53") (pin "C") (pinfunction "C_C") (pintype "passive"))
      (node (ref "LED61") (pin "C") (pinfunction "C_C") (pintype "passive"))
      (node (ref "U2") (pin "3") (pinfunction "DIG4_3") (pintype "output"))
    )
    (net (code "25") (name "Net-(U2-DIG5)") (class "Default")
      (node (ref "LED14") (pin "C") (pinfunction "C_C") (pintype "passive"))
      (node (ref "LED22") (pin "C") (pinfunction "C_C") (pintype "passive"))
      (node (ref "LED30") (pin "C") (pinfunction "C_C") (pintype "passive"))
      (node (ref "LED38") (pin "C") (pinfunction "C_C") (pintype "passive"))
      (node (ref "LED46") (pin "C") (pinfunction "C_C") (pintype "passive"))
      (node (ref "LED54") (pin "C") (pinfunction "C_C") (pintype "passive"))
      (node (ref "LED6") (pin "C") (pinfunction "C_C") (pintype "passive"))
      (node (ref "LED62") (pin "C") (pinfunction "C_C") (pintype "passive"))
      (node (ref "U2") (pin "10") (pinfunction "DIG5_10") (pintype "output"))
    )
    (net (code "26") (name "Net-(U2-DIG6)") (class "Default")
      (node (ref "LED15") (pin "C") (pinfunction "C_C") (pintype "passive"))
      (node (ref "LED23") (pin "C") (pinfunction "C_C") (pintype "passive"))
      (node (ref "LED31") (pin "C") (pinfunction "C_C") (pintype "passive"))
      (node (ref "LED39") (pin "C") (pinfunction "C_C") (pintype "passive"))
      (node (ref "LED47") (pin "C") (pinfunction "C_C") (pintype "passive"))
      (node (ref "LED55") (pin "C") (pinfunction "C_C") (pintype "passive"))
      (node (ref "LED63") (pin "C") (pinfunction "C_C") (pintype "passive"))
      (node (ref "LED7") (pin "C") (pinfunction "C_C") (pintype "passive"))
      (node (ref "U2") (pin "5") (pinfunction "DIG6_5") (pintype "output"))
    )
    (net (code "27") (name "Net-(U2-DIG7)") (class "Default")
      (node (ref "LED16") (pin "C") (pinfunction "C_C") (pintype "passive"))
      (node (ref "LED24") (pin "C") (pinfunction "C_C") (pintype "passive"))
      (node (ref "LED32") (pin "C") (pinfunction "C_C") (pintype "passive"))
      (node (ref "LED40") (pin "C") (pinfunction "C_C") (pintype "passive"))
      (node (ref "LED48") (pin "C") (pinfunction "C_C") (pintype "passive"))
      (node (ref "LED56") (pin "C") (pinfunction "C_C") (pintype "passive"))
      (node (ref "LED64") (pin "C") (pinfunction "C_C") (pintype "passive"))
      (node (ref "LED8") (pin "C") (pinfunction "C_C") (pintype "passive"))
      (node (ref "U2") (pin "8") (pinfunction "DIG7_8") (pintype "output"))
    )
    (net (code "28") (name "Net-(U2-DIN)") (class "Default")
      (node (ref "U2") (pin "1") (pinfunction "DIN_1") (pintype "input"))
      (node (ref "U3") (pin "24") (pinfunction "DOUT_24") (pintype "output"))
    )
    (net (code "29") (name "Net-(U2-ISET)") (class "Default")
      (node (ref "R1") (pin "2") (pinfunction "2_2") (pintype "passive"))
      (node (ref "U2") (pin "18") (pinfunction "ISET_18") (pintype "input"))
    )
    (net (code "30") (name "Net-(U2-SEGA)") (class "Default")
      (node (ref "LED1") (pin "A") (pinfunction "A_A") (pintype "passive"))
      (node (ref "LED2") (pin "A") (pinfunction "A_A") (pintype "passive"))
      (node (ref "LED3") (pin "A") (pinfunction "A_A") (pintype "passive"))
      (node (ref "LED4") (pin "A") (pinfunction "A_A") (pintype "passive"))
      (node (ref "LED5") (pin "A") (pinfunction "A_A") (pintype "passive"))
      (node (ref "LED6") (pin "A") (pinfunction "A_A") (pintype "passive"))
      (node (ref "LED7") (pin "A") (pinfunction "A_A") (pintype "passive"))
      (node (ref "LED8") (pin "A") (pinfunction "A_A") (pintype "passive"))
      (node (ref "U2") (pin "14") (pinfunction "SEGA_14") (pintype "output"))
    )
    (net (code "31") (name "Net-(U2-SEGB)") (class "Default")
      (node (ref "LED10") (pin "A") (pinfunction "A_A") (pintype "passive"))
      (node (ref "LED11") (pin "A") (pinfunction "A_A") (pintype "passive"))
      (node (ref "LED12") (pin "A") (pinfunction "A_A") (pintype "passive"))
      (node (ref "LED13") (pin "A") (pinfunction "A_A") (pintype "passive"))
      (node (ref "LED14") (pin "A") (pinfunction "A_A") (pintype "passive"))
      (node (ref "LED15") (pin "A") (pinfunction "A_A") (pintype "passive"))
      (node (ref "LED16") (pin "A") (pinfunction "A_A") (pintype "passive"))
      (node (ref "LED9") (pin "A") (pinfunction "A_A") (pintype "passive"))
      (node (ref "U2") (pin "16") (pinfunction "SEGB_16") (pintype "output"))
    )
    (net (code "32") (name "Net-(U2-SEGC)") (class "Default")
      (node (ref "LED17") (pin "A") (pinfunction "A_A") (pintype "passive"))
      (node (ref "LED18") (pin "A") (pinfunction "A_A") (pintype "passive"))
      (node (ref "LED19") (pin "A") (pinfunction "A_A") (pintype "passive"))
      (node (ref "LED20") (pin "A") (pinfunction "A_A") (pintype "passive"))
      (node (ref "LED21") (pin "A") (pinfunction "A_A") (pintype "passive"))
      (node (ref "LED22") (pin "A") (pinfunction "A_A") (pintype "passive"))
      (node (ref "LED23") (pin "A") (pinfunction "A_A") (pintype "passive"))
      (node (ref "LED24") (pin "A") (pinfunction "A_A") (pintype "passive"))
      (node (ref "U2") (pin "20") (pinfunction "SEGC_20") (pintype "output"))
    )
    (net (code "33") (name "Net-(U2-SEGD)") (class "Default")
      (node (ref "LED25") (pin "A") (pinfunction "A_A") (pintype "passive"))
      (node (ref "LED26") (pin "A") (pinfunction "A_A") (pintype "passive"))
      (node (ref "LED27") (pin "A") (pinfunction "A_A") (pintype "passive"))
      (node (ref "LED28") (pin "A") (pinfunction "A_A") (pintype "passive"))
      (node (ref "LED29") (pin "A") (pinfunction "A_A") (pintype "passive"))
      (node (ref "LED30") (pin "A") (pinfunction "A_A") (pintype "passive"))
      (node (ref "LED31") (pin "A") (pinfunction "A_A") (pintype "passive"))
      (node (ref "LED32") (pin "A") (pinfunction "A_A") (pintype "passive"))
      (node (ref "U2") (pin "23") (pinfunction "SEGD_23") (pintype "output"))
    )
    (net (code "34") (name "Net-(U2-SEGDP)") (class "Default")
      (node (ref "LED57") (pin "A") (pinfunction "A_A") (pintype "passive"))
      (node (ref "LED58") (pin "A") (pinfunction "A_A") (pintype "passive"))
      (node (ref "LED59") (pin "A") (pinfunction "A_A") (pintype "passive"))
      (node (ref "LED60") (pin "A") (pinfunction "A_A") (pintype "passive"))
      (node (ref "LED61") (pin "A") (pinfunction "A_A") (pintype "passive"))
      (node (ref "LED62") (pin "A") (pinfunction "A_A") (pintype "passive"))
      (node (ref "LED63") (pin "A") (pinfunction "A_A") (pintype "passive"))
      (node (ref "LED64") (pin "A") (pinfunction "A_A") (pintype "passive"))
      (node (ref "U2") (pin "22") (pinfunction "SEGDP_22") (pintype "output"))
    )
    (net (code "35") (name "Net-(U2-SEGE)") (class "Default")
      (node (ref "LED33") (pin "A") (pinfunction "A_A") (pintype "passive"))
      (node (ref "LED34") (pin "A") (pinfunction "A_A") (pintype "passive"))
      (node (ref "LED35") (pin "A") (pinfunction "A_A") (pintype "passive"))
      (node (ref "LED36") (pin "A") (pinfunction "A_A") (pintype "passive"))
      (node (ref "LED37") (pin "A") (pinfunction "A_A") (pintype "passive"))
      (node (ref "LED38") (pin "A") (pinfunction "A_A") (pintype "passive"))
      (node (ref "LED39") (pin "A") (pinfunction "A_A") (pintype "passive"))
      (node (ref "LED40") (pin "A") (pinfunction "A_A") (pintype "passive"))
      (node (ref "U2") (pin "21") (pinfunction "SEGE_21") (pintype "output"))
    )
    (net (code "36") (name "Net-(U2-SEGF)") (class "Default")
      (node (ref "LED41") (pin "A") (pinfunction "A_A") (pintype "passive"))
      (node (ref "LED42") (pin "A") (pinfunction "A_A") (pintype "passive"))
      (node (ref "LED43") (pin "A") (pinfunction "A_A") (pintype "passive"))
      (node (ref "LED44") (pin "A") (pinfunction "A_A") (pintype "passive"))
      (node (ref "LED45") (pin "A") (pinfunction "A_A") (pintype "passive"))
      (node (ref "LED46") (pin "A") (pinfunction "A_A") (pintype "passive"))
      (node (ref "LED47") (pin "A") (pinfunction "A_A") (pintype "passive"))
      (node (ref "LED48") (pin "A") (pinfunction "A_A") (pintype "passive"))
      (node (ref "U2") (pin "15") (pinfunction "SEGF_15") (pintype "output"))
    )
    (net (code "37") (name "Net-(U2-SEGG)") (class "Default")
      (node (ref "LED49") (pin "A") (pinfunction "A_A") (pintype "passive"))
      (node (ref "LED50") (pin "A") (pinfunction "A_A") (pintype "passive"))
      (node (ref "LED51") (pin "A") (pinfunction "A_A") (pintype "passive"))
      (node (ref "LED52") (pin "A") (pinfunction "A_A") (pintype "passive"))
      (node (ref "LED53") (pin "A") (pinfunction "A_A") (pintype "passive"))
      (node (ref "LED54") (pin "A") (pinfunction "A_A") (pintype "passive"))
      (node (ref "LED55") (pin "A") (pinfunction "A_A") (pintype "passive"))
      (node (ref "LED56") (pin "A") (pinfunction "A_A") (pintype "passive"))
      (node (ref "U2") (pin "17") (pinfunction "SEGG_17") (pintype "output"))
    )
    (net (code "38") (name "Net-(U3-DIG0)") (class "Default")
      (node (ref "LED105") (pin "C") (pinfunction "C_C") (pintype "passive"))
      (node (ref "LED65") (pin "C") (pinfunction "C_C") (pintype "passive"))
      (node (ref "LED73") (pin "C") (pinfunction "C_C") (pintype "passive"))
      (node (ref "LED81") (pin "C") (pinfunction "C_C") (pintype "passive"))
      (node (ref "LED89") (pin "C") (pinfunction "C_C") (pintype "passive"))
      (node (ref "LED97") (pin "C") (pinfunction "C_C") (pintype "passive"))
      (node (ref "U3") (pin "2") (pinfunction "DIG0_2") (pintype "output"))
    )
    (net (code "39") (name "Net-(U3-DIG1)") (class "Default")
      (node (ref "LED106") (pin "C") (pinfunction "C_C") (pintype "passive"))
      (node (ref "LED66") (pin "C") (pinfunction "C_C") (pintype "passive"))
      (node (ref "LED74") (pin "C") (pinfunction "C_C") (pintype "passive"))
      (node (ref "LED82") (pin "C") (pinfunction "C_C") (pintype "passive"))
      (node (ref "LED90") (pin "C") (pinfunction "C_C") (pintype "passive"))
      (node (ref "LED98") (pin "C") (pinfunction "C_C") (pintype "passive"))
      (node (ref "U3") (pin "11") (pinfunction "DIG1_11") (pintype "output"))
    )
    (net (code "40") (name "Net-(U3-DIG2)") (class "Default")
      (node (ref "LED107") (pin "C") (pinfunction "C_C") (pintype "passive"))
      (node (ref "LED67") (pin "C") (pinfunction "C_C") (pintype "passive"))
      (node (ref "LED75") (pin "C") (pinfunction "C_C") (pintype "passive"))
      (node (ref "LED83") (pin "C") (pinfunction "C_C") (pintype "passive"))
      (node (ref "LED91") (pin "C") (pinfunction "C_C") (pintype "passive"))
      (node (ref "LED99") (pin "C") (pinfunction "C_C") (pintype "passive"))
      (node (ref "U3") (pin "6") (pinfunction "DIG2_6") (pintype "output"))
    )
    (net (code "41") (name "Net-(U3-DIG3)") (class "Default")
      (node (ref "LED100") (pin "C") (pinfunction "C_C") (pintype "passive"))
      (node (ref "LED108") (pin "C") (pinfunction "C_C") (pintype "passive"))
      (node (ref "LED68") (pin "C") (pinfunction "C_C") (pintype "passive"))
      (node (ref "LED76") (pin "C") (pinfunction "C_C") (pintype "passive"))
      (node (ref "LED84") (pin "C") (pinfunction "C_C") (pintype "passive"))
      (node (ref "LED92") (pin "C") (pinfunction "C_C") (pintype "passive"))
      (node (ref "U3") (pin "7") (pinfunction "DIG3_7") (pintype "output"))
    )
    (net (code "42") (name "Net-(U3-DIG4)") (class "Default")
      (node (ref "LED101") (pin "C") (pinfunction "C_C") (pintype "passive"))
      (node (ref "LED109") (pin "C") (pinfunction "C_C") (pintype "passive"))
      (node (ref "LED69") (pin "C") (pinfunction "C_C") (pintype "passive"))
      (node (ref "LED77") (pin "C") (pinfunction "C_C") (pintype "passive"))
      (node (ref "LED85") (pin "C") (pinfunction "C_C") (pintype "passive"))
      (node (ref "LED93") (pin "C") (pinfunction "C_C") (pintype "passive"))
      (node (ref "U3") (pin "3") (pinfunction "DIG4_3") (pintype "output"))
    )
    (net (code "43") (name "Net-(U3-DIG5)") (class "Default")
      (node (ref "LED102") (pin "C") (pinfunction "C_C") (pintype "passive"))
      (node (ref "LED110") (pin "C") (pinfunction "C_C") (pintype "passive"))
      (node (ref "LED70") (pin "C") (pinfunction "C_C") (pintype "passive"))
      (node (ref "LED78") (pin "C") (pinfunction "C_C") (pintype "passive"))
      (node (ref "LED86") (pin "C") (pinfunction "C_C") (pintype "passive"))
      (node (ref "LED94") (pin "C") (pinfunction "C_C") (pintype "passive"))
      (node (ref "U3") (pin "10") (pinfunction "DIG5_10") (pintype "output"))
    )
    (net (code "44") (name "Net-(U3-DIG6)") (class "Default")
      (node (ref "LED103") (pin "C") (pinfunction "C_C") (pintype "passive"))
      (node (ref "LED71") (pin "C") (pinfunction "C_C") (pintype "passive"))
      (node (ref "LED79") (pin "C") (pinfunction "C_C") (pintype "passive"))
      (node (ref "LED87") (pin "C") (pinfunction "C_C") (pintype "passive"))
      (node (ref "LED95") (pin "C") (pinfunction "C_C") (pintype "passive"))
      (node (ref "U3") (pin "5") (pinfunction "DIG6_5") (pintype "output"))
    )
    (net (code "45") (name "Net-(U3-DIG7)") (class "Default")
      (node (ref "LED104") (pin "C") (pinfunction "C_C") (pintype "passive"))
      (node (ref "LED72") (pin "C") (pinfunction "C_C") (pintype "passive"))
      (node (ref "LED80") (pin "C") (pinfunction "C_C") (pintype "passive"))
      (node (ref "LED88") (pin "C") (pinfunction "C_C") (pintype "passive"))
      (node (ref "LED96") (pin "C") (pinfunction "C_C") (pintype "passive"))
      (node (ref "U3") (pin "8") (pinfunction "DIG7_8") (pintype "output"))
    )
    (net (code "46") (name "Net-(U3-ISET)") (class "Default")
      (node (ref "R3") (pin "2") (pinfunction "2_2") (pintype "passive"))
      (node (ref "U3") (pin "18") (pinfunction "ISET_18") (pintype "input"))
    )
    (net (code "47") (name "Net-(U3-SEGA)") (class "Default")
      (node (ref "LED65") (pin "A") (pinfunction "A_A") (pintype "passive"))
      (node (ref "LED66") (pin "A") (pinfunction "A_A") (pintype "passive"))
      (node (ref "LED67") (pin "A") (pinfunction "A_A") (pintype "passive"))
      (node (ref "LED68") (pin "A") (pinfunction "A_A") (pintype "passive"))
      (node (ref "LED69") (pin "A") (pinfunction "A_A") (pintype "passive"))
      (node (ref "LED70") (pin "A") (pinfunction "A_A") (pintype "passive"))
      (node (ref "LED71") (pin "A") (pinfunction "A_A") (pintype "passive"))
      (node (ref "LED72") (pin "A") (pinfunction "A_A") (pintype "passive"))
      (node (ref "U3") (pin "14") (pinfunction "SEGA_14") (pintype "output"))
    )
    (net (code "48") (name "Net-(U3-SEGB)") (class "Default")
      (node (ref "LED73") (pin "A") (pinfunction "A_A") (pintype "passive"))
      (node (ref "LED74") (pin "A") (pinfunction "A_A") (pintype "passive"))
      (node (ref "LED75") (pin "A") (pinfunction "A_A") (pintype "passive"))
      (node (ref "LED76") (pin "A") (pinfunction "A_A") (pintype "passive"))
      (node (ref "LED77") (pin "A") (pinfunction "A_A") (pintype "passive"))
      (node (ref "LED78") (pin "A") (pinfunction "A_A") (pintype "passive"))
      (node (ref "LED79") (pin "A") (pinfunction "A_A") (pintype "passive"))
      (node (ref "LED80") (pin "A") (pinfunction "A_A") (pintype "passive"))
      (node (ref "U3") (pin "16") (pinfunction "SEGB_16") (pintype "output"))
    )
    (net (code "49") (name "Net-(U3-SEGC)") (class "Default")
      (node (ref "LED81") (pin "A") (pinfunction "A_A") (pintype "passive"))
      (node (ref "LED82") (pin "A") (pinfunction "A_A") (pintype "passive"))
      (node (ref "LED83") (pin "A") (pinfunction "A_A") (pintype "passive"))
      (node (ref "LED84") (pin "A") (pinfunction "A_A") (pintype "passive"))
      (node (ref "LED85") (pin "A") (pinfunction "A_A") (pintype "passive"))
      (node (ref "LED86") (pin "A") (pinfunction "A_A") (pintype "passive"))
      (node (ref "LED87") (pin "A") (pinfunction "A_A") (pintype "passive"))
      (node (ref "LED88") (pin "A") (pinfunction "A_A") (pintype "passive"))
      (node (ref "U3") (pin "20") (pinfunction "SEGC_20") (pintype "output"))
    )
    (net (code "50") (name "Net-(U3-SEGD)") (class "Default")
      (node (ref "LED89") (pin "A") (pinfunction "A_A") (pintype "passive"))
      (node (ref "LED90") (pin "A") (pinfunction "A_A") (pintype "passive"))
      (node (ref "LED91") (pin "A") (pinfunction "A_A") (pintype "passive"))
      (node (ref "LED92") (pin "A") (pinfunction "A_A") (pintype "passive"))
      (node (ref "LED93") (pin "A") (pinfunction "A_A") (pintype "passive"))
      (node (ref "LED94") (pin "A") (pinfunction "A_A") (pintype "passive"))
      (node (ref "LED95") (pin "A") (pinfunction "A_A") (pintype "passive"))
      (node (ref "LED96") (pin "A") (pinfunction "A_A") (pintype "passive"))
      (node (ref "U3") (pin "23") (pinfunction "SEGD_23") (pintype "output"))
    )
    (net (code "51") (name "Net-(U3-SEGE)") (class "Default")
      (node (ref "LED100") (pin "A") (pinfunction "A_A") (pintype "passive"))
      (node (ref "LED101") (pin "A") (pinfunction "A_A") (pintype "passive"))
      (node (ref "LED102") (pin "A") (pinfunction "A_A") (pintype "passive"))
      (node (ref "LED103") (pin "A") (pinfunction "A_A") (pintype "passive"))
      (node (ref "LED104") (pin "A") (pinfunction "A_A") (pintype "passive"))
      (node (ref "LED97") (pin "A") (pinfunction "A_A") (pintype "passive"))
      (node (ref "LED98") (pin "A") (pinfunction "A_A") (pintype "passive"))
      (node (ref "LED99") (pin "A") (pinfunction "A_A") (pintype "passive"))
      (node (ref "U3") (pin "21") (pinfunction "SEGE_21") (pintype "output"))
    )
    (net (code "52") (name "Net-(U3-SEGF)") (class "Default")
      (node (ref "LED105") (pin "A") (pinfunction "A_A") (pintype "passive"))
      (node (ref "LED106") (pin "A") (pinfunction "A_A") (pintype "passive"))
      (node (ref "LED107") (pin "A") (pinfunction "A_A") (pintype "passive"))
      (node (ref "LED108") (pin "A") (pinfunction "A_A") (pintype "passive"))
      (node (ref "LED109") (pin "A") (pinfunction "A_A") (pintype "passive"))
      (node (ref "LED110") (pin "A") (pinfunction "A_A") (pintype "passive"))
      (node (ref "U3") (pin "15") (pinfunction "SEGF_15") (pintype "output"))
    )
    (net (code "53") (name "RST") (class "Default")
      (node (ref "C8") (pin "1") (pinfunction "1_1") (pintype "passive"))
      (node (ref "MDL1") (pin "1") (pinfunction "REST_1") (pintype "bidirectional"))
      (node (ref "R5") (pin "1") (pinfunction "1_1") (pintype "passive"))
      (node (ref "T1") (pin "C") (pinfunction "C_C") (pintype "passive"))
    )
    (net (code "54") (name "RXD") (class "Default")
      (node (ref "JP3") (pin "6") (pinfunction "6_6") (pintype "passive"))
      (node (ref "MDL1") (pin "15") (pinfunction "RXD_15") (pintype "bidirectional"))
    )
    (net (code "55") (name "SCL") (class "Default")
      (node (ref "MDL1") (pin "14") (pinfunction "GPIO5_14") (pintype "bidirectional"))
      (node (ref "U$3") (pin "SCL") (pinfunction "SCL_SCL") (pintype "bidirectional"))
    )
    (net (code "56") (name "SDA") (class "Default")
      (node (ref "MDL1") (pin "13") (pinfunction "GPIO4_13") (pintype "bidirectional"))
      (node (ref "U$3") (pin "SDA") (pinfunction "SDA_SDA") (pintype "bidirectional"))
    )
    (net (code "57") (name "TXD") (class "Default")
      (node (ref "JP3") (pin "7") (pinfunction "7_7") (pintype "passive"))
      (node (ref "MDL1") (pin "16") (pinfunction "TXD_16") (pintype "bidirectional"))
    )
    (net (code "58") (name "unconnected-(MDL1-ADC-Pad2)") (class "Default")
      (node (ref "MDL1") (pin "2") (pinfunction "ADC_2") (pintype "bidirectional"))
    )
    (net (code "59") (name "unconnected-(MDL1-CS0-Pad17)") (class "Default")
      (node (ref "MDL1") (pin "17") (pinfunction "CS0_17") (pintype "bidirectional"))
    )
    (net (code "60") (name "unconnected-(MDL1-GPIO9-Pad19)") (class "Default")
      (node (ref "MDL1") (pin "19") (pinfunction "GPIO9_19") (pintype "bidirectional"))
    )
    (net (code "61") (name "unconnected-(MDL1-GPIO10-Pad20)") (class "Default")
      (node (ref "MDL1") (pin "20") (pinfunction "GPIO10_20") (pintype "bidirectional"))
    )
    (net (code "62") (name "unconnected-(MDL1-MISO-Pad18)") (class "Default")
      (node (ref "MDL1") (pin "18") (pinfunction "MISO_18") (pintype "bidirectional"))
    )
    (net (code "63") (name "unconnected-(MDL1-MOSI-Pad21)") (class "Default")
      (node (ref "MDL1") (pin "21") (pinfunction "MOSI_21") (pintype "bidirectional"))
    )
    (net (code "64") (name "unconnected-(MDL1-SCLK-Pad22)") (class "Default")
      (node (ref "MDL1") (pin "22") (pinfunction "SCLK_22") (pintype "bidirectional"))
    )
    (net (code "65") (name "unconnected-(U$3-DS-PadDS@2)") (class "Default")
      (node (ref "U$3") (pin "DS@2") (pinfunction "DS_DS@2") (pintype "bidirectional"))
    )
    (net (code "66") (name "unconnected-(U$3-GND-PadGND@2)") (class "Default")
      (node (ref "U$3") (pin "GND@2") (pinfunction "GND_GND@2") (pintype "bidirectional"))
    )
    (net (code "67") (name "unconnected-(U$3-PadBAT)") (class "Default")
      (node (ref "U$3") (pin "BAT") (pinfunction "BAT_BAT") (pintype "bidirectional"))
    )
    (net (code "68") (name "unconnected-(U$3-PadDS)") (class "Default")
      (node (ref "U$3") (pin "DS") (pinfunction "DS_DS") (pintype "bidirectional"))
    )
    (net (code "69") (name "unconnected-(U$3-PadSQ)") (class "Default")
      (node (ref "U$3") (pin "SQ") (pinfunction "SQ_SQ") (pintype "bidirectional"))
    )
    (net (code "70") (name "unconnected-(U$3-SCL-PadSCL@2)") (class "Default")
      (node (ref "U$3") (pin "SCL@2") (pinfunction "SCL_SCL@2") (pintype "bidirectional"))
    )
    (net (code "71") (name "unconnected-(U$3-SDA-PadSDA@2)") (class "Default")
      (node (ref "U$3") (pin "SDA@2") (pinfunction "SDA_SDA@2") (pintype "bidirectional"))
    )
    (net (code "72") (name "unconnected-(U$3-VCC-PadVCC@2)") (class "Default")
      (node (ref "U$3") (pin "VCC@2") (pinfunction "VCC_VCC@2") (pintype "bidirectional"))
    )
    (net (code "73") (name "unconnected-(U2-DOUT-Pad24)") (class "Default")
      (node (ref "U2") (pin "24") (pinfunction "DOUT_24") (pintype "output"))
    )
    (net (code "74") (name "unconnected-(U3-SEGDP-Pad22)") (class "Default")
      (node (ref "U3") (pin "22") (pinfunction "SEGDP_22") (pintype "output"))
    )
    (net (code "75") (name "unconnected-(U3-SEGG-Pad17)") (class "Default")
      (node (ref "U3") (pin "17") (pinfunction "SEGG_17") (pintype "output"))
    )
  )
)
